# amg8833.net
KiCad netlist of a schematic drawn in EAGLE
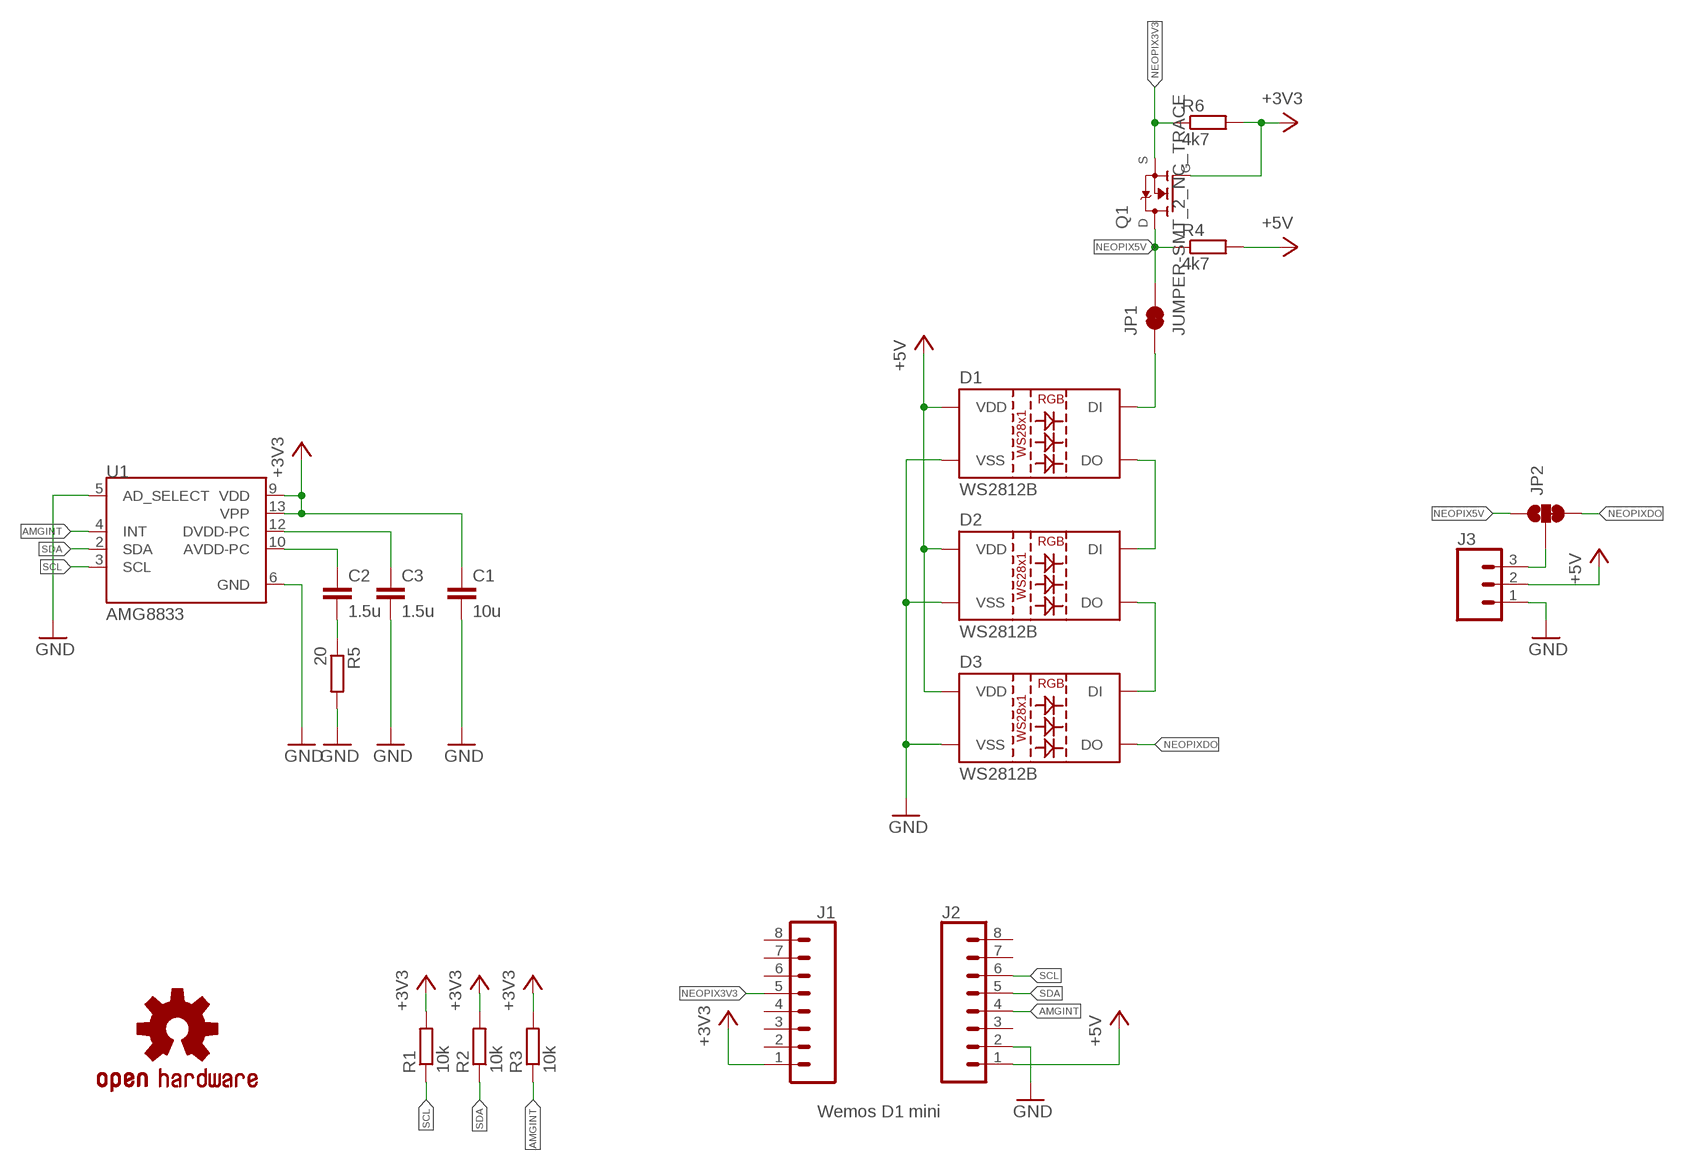
[diagram p0: schematic, sheet 1]

(export (version "E")
  (design (tool "Eeschema 10.0.6"))
  (components
    (comp (ref "C1")
      (value "10u")
      (footprint "eagle-import:C0603")
      (libsource (lib "eagle-import") (part "C-EUC0603"))
    )
    (comp (ref "C2")
      (value "1.5u")
      (footprint "eagle-import:C0603")
      (libsource (lib "eagle-import") (part "C-EUC0603"))
    )
    (comp (ref "C3")
      (value "1.5u")
      (footprint "eagle-import:C0603")
      (libsource (lib "eagle-import") (part "C-EUC0603"))
    )
    (comp (ref "D1")
      (value "WS2812B")
      (footprint "eagle-import:WS2812B")
      (libsource (lib "eagle-import") (part "WS2812B"))
    )
    (comp (ref "D2")
      (value "WS2812B")
      (footprint "eagle-import:WS2812B")
      (libsource (lib "eagle-import") (part "WS2812B"))
    )
    (comp (ref "D3")
      (value "WS2812B")
      (footprint "eagle-import:WS2812B")
      (libsource (lib "eagle-import") (part "WS2812B"))
    )
    (comp (ref "J1")
      (value "CONN_08")
      (footprint "eagle-import:1X08_LOCK_NO_SILK")
      (libsource (lib "eagle-import") (part "CONN_08"))
    )
    (comp (ref "J2")
      (value "CONN_08")
      (footprint "eagle-import:1X08_LOCK_NO_SILK")
      (libsource (lib "eagle-import") (part "CONN_08"))
    )
    (comp (ref "J3")
      (value "CONN_03SCREWTERMINAL-3.5MM-3-NS")
      (footprint "eagle-import:SCREWTERMINAL-3.5MM-3-NS")
      (libsource (lib "eagle-import") (part "CONN_03SCREWTERMINAL-3.5MM-3-NS"))
    )
    (comp (ref "JP1")
      (value "JUMPER-SMT_2_NC_TRACE")
      (footprint "eagle-import:SMT-JUMPER_2_NC_TRACE_SILK")
      (libsource (lib "eagle-import") (part "JUMPER-SMT_2_NC_TRACE"))
    )
    (comp (ref "JP2")
      (value "JUMPER-SMT_3_1-NC_TRACE")
      (footprint "eagle-import:SMT-JUMPER_3_1-NC_TRACE_SILK")
      (libsource (lib "eagle-import") (part "JUMPER-SMT_3_1-NC_TRACE"))
    )
    (comp (ref "LOGO1")
      (value "OSHW-LOGO")
      (footprint "eagle-import:OSHW-LOGO-M")
      (libsource (lib "eagle-import") (part "OSHW-LOGO"))
    )
    (comp (ref "Q1")
      (value "BSN20,215")
      (footprint "eagle-import:BSN20_215")
      (fields (field (name "MF") "NXP Semiconductors"))
      (libsource (lib "eagle-import") (part "BSN20,215"))
    )
    (comp (ref "R1")
      (value "10k")
      (footprint "eagle-import:R0603")
      (libsource (lib "eagle-import") (part "R-EU_R0603"))
    )
    (comp (ref "R2")
      (value "10k")
      (footprint "eagle-import:R0603")
      (libsource (lib "eagle-import") (part "R-EU_R0603"))
    )
    (comp (ref "R3")
      (value "10k")
      (footprint "eagle-import:R0603")
      (libsource (lib "eagle-import") (part "R-EU_R0603"))
    )
    (comp (ref "R4")
      (value "4k7")
      (footprint "eagle-import:R0603")
      (libsource (lib "eagle-import") (part "R-EU_R0603"))
    )
    (comp (ref "R5")
      (value "20")
      (footprint "eagle-import:R0603")
      (libsource (lib "eagle-import") (part "R-EU_R0603"))
    )
    (comp (ref "R6")
      (value "4k7")
      (footprint "eagle-import:R0603")
      (libsource (lib "eagle-import") (part "R-EU_R0603"))
    )
    (comp (ref "U1")
      (value "AMG8833")
      (footprint "eagle-import:XDCR_AMG8833")
      (fields (field (name "DIGI-KEY_PART_NUMBER") "P19002CT-ND") (field (name "MF") "Panasonic"))
      (libsource (lib "eagle-import") (part "AMG8833"))
    )
  )
  (nets
    (net (code "1") (name "+3V3") (class "Default")
      (node (ref "C1") (pin "1") (pinfunction "1_1") (pintype "passive"))
      (node (ref "J1") (pin "1") (pinfunction "1_1") (pintype "passive"))
      (node (ref "Q1") (pin "1") (pinfunction "G_1") (pintype "passive"))
      (node (ref "R1") (pin "2") (pinfunction "2_2") (pintype "passive"))
      (node (ref "R2") (pin "2") (pinfunction "2_2") (pintype "passive"))
      (node (ref "R3") (pin "2") (pinfunction "2_2") (pintype "passive"))
      (node (ref "R6") (pin "2") (pinfunction "2_2") (pintype "passive"))
      (node (ref "U1") (pin "13") (pinfunction "VPP_13") (pintype "power_in"))
      (node (ref "U1") (pin "9") (pinfunction "VDD_9") (pintype "power_in"))
    )
    (net (code "2") (name "+5V") (class "Default")
      (node (ref "D1") (pin "1") (pinfunction "VDD_1") (pintype "bidirectional"))
      (node (ref "D2") (pin "1") (pinfunction "VDD_1") (pintype "bidirectional"))
      (node (ref "D3") (pin "1") (pinfunction "VDD_1") (pintype "bidirectional"))
      (node (ref "J2") (pin "1") (pinfunction "1_1") (pintype "passive"))
      (node (ref "J3") (pin "2") (pinfunction "2_2") (pintype "passive"))
      (node (ref "R4") (pin "2") (pinfunction "2_2") (pintype "passive"))
    )
    (net (code "3") (name "AMGINT") (class "Default")
      (node (ref "J2") (pin "4") (pinfunction "4_4") (pintype "passive"))
      (node (ref "R3") (pin "1") (pinfunction "1_1") (pintype "passive"))
      (node (ref "U1") (pin "4") (pinfunction "INT_4") (pintype "bidirectional"))
    )
    (net (code "4") (name "GND") (class "Default")
      (node (ref "C1") (pin "2") (pinfunction "2_2") (pintype "passive"))
      (node (ref "C3") (pin "2") (pinfunction "2_2") (pintype "passive"))
      (node (ref "D1") (pin "3") (pinfunction "VSS_3") (pintype "bidirectional"))
      (node (ref "D2") (pin "3") (pinfunction "VSS_3") (pintype "bidirectional"))
      (node (ref "D3") (pin "3") (pinfunction "VSS_3") (pintype "bidirectional"))
      (node (ref "J2") (pin "2") (pinfunction "2_2") (pintype "passive"))
      (node (ref "J3") (pin "1") (pinfunction "1_1") (pintype "passive"))
      (node (ref "R5") (pin "2") (pinfunction "2_2") (pintype "passive"))
      (node (ref "U1") (pin "5") (pinfunction "AD_SELECT_5") (pintype "input"))
      (node (ref "U1") (pin "6") (pinfunction "GND_6") (pintype "power_in"))
    )
    (net (code "5") (name "NEOPIX3V3") (class "Default")
      (node (ref "J1") (pin "5") (pinfunction "5_5") (pintype "passive"))
      (node (ref "Q1") (pin "2") (pinfunction "S_2") (pintype "passive"))
      (node (ref "R6") (pin "1") (pinfunction "1_1") (pintype "passive"))
    )
    (net (code "6") (name "NEOPIX5V") (class "Default")
      (node (ref "JP1") (pin "2") (pinfunction "2_2") (pintype "passive"))
      (node (ref "JP2") (pin "1") (pinfunction "1_1") (pintype "passive"))
      (node (ref "Q1") (pin "3") (pinfunction "D_3") (pintype "passive"))
      (node (ref "R4") (pin "1") (pinfunction "1_1") (pintype "passive"))
    )
    (net (code "7") (name "NEOPIXDO") (class "Default")
      (node (ref "D3") (pin "2") (pinfunction "DO_2") (pintype "bidirectional"))
      (node (ref "JP2") (pin "3") (pinfunction "3_3") (pintype "passive"))
    )
    (net (code "8") (name "Net-(C2-Pad2)") (class "Default")
      (node (ref "C2") (pin "2") (pinfunction "2_2") (pintype "passive"))
      (node (ref "R5") (pin "1") (pinfunction "1_1") (pintype "passive"))
    )
    (net (code "9") (name "Net-(D1-DI)") (class "Default")
      (node (ref "D1") (pin "4") (pinfunction "DI_4") (pintype "bidirectional"))
      (node (ref "JP1") (pin "1") (pinfunction "1_1") (pintype "passive"))
    )
    (net (code "10") (name "Net-(D1-DO)") (class "Default")
      (node (ref "D1") (pin "2") (pinfunction "DO_2") (pintype "bidirectional"))
      (node (ref "D2") (pin "4") (pinfunction "DI_4") (pintype "bidirectional"))
    )
    (net (code "11") (name "Net-(D2-DO)") (class "Default")
      (node (ref "D2") (pin "2") (pinfunction "DO_2") (pintype "bidirectional"))
      (node (ref "D3") (pin "4") (pinfunction "DI_4") (pintype "bidirectional"))
    )
    (net (code "12") (name "Net-(J3-Pad3)") (class "Default")
      (node (ref "J3") (pin "3") (pinfunction "3_3") (pintype "passive"))
      (node (ref "JP2") (pin "2") (pinfunction "2_2") (pintype "passive"))
    )
    (net (code "13") (name "Net-(U1-AVDD-PC)") (class "Default")
      (node (ref "C2") (pin "1") (pinfunction "1_1") (pintype "passive"))
      (node (ref "U1") (pin "10") (pinfunction "AVDD-PC_10") (pintype "power_in"))
    )
    (net (code "14") (name "Net-(U1-DVDD-PC)") (class "Default")
      (node (ref "C3") (pin "1") (pinfunction "1_1") (pintype "passive"))
      (node (ref "U1") (pin "12") (pinfunction "DVDD-PC_12") (pintype "power_in"))
    )
    (net (code "15") (name "SCL") (class "Default")
      (node (ref "J2") (pin "6") (pinfunction "6_6") (pintype "passive"))
      (node (ref "R1") (pin "1") (pinfunction "1_1") (pintype "passive"))
      (node (ref "U1") (pin "3") (pinfunction "SCL_3") (pintype "bidirectional"))
    )
    (net (code "16") (name "SDA") (class "Default")
      (node (ref "J2") (pin "5") (pinfunction "5_5") (pintype "passive"))
      (node (ref "R2") (pin "1") (pinfunction "1_1") (pintype "passive"))
      (node (ref "U1") (pin "2") (pinfunction "SDA_2") (pintype "bidirectional"))
    )
    (net (code "17") (name "unconnected-(J1-Pad2)") (class "Default")
      (node (ref "J1") (pin "2") (pinfunction "2_2") (pintype "passive"))
    )
    (net (code "18") (name "unconnected-(J1-Pad3)") (class "Default")
      (node (ref "J1") (pin "3") (pinfunction "3_3") (pintype "passive"))
    )
    (net (code "19") (name "unconnected-(J1-Pad4)") (class "Default")
      (node (ref "J1") (pin "4") (pinfunction "4_4") (pintype "passive"))
    )
    (net (code "20") (name "unconnected-(J1-Pad6)") (class "Default")
      (node (ref "J1") (pin "6") (pinfunction "6_6") (pintype "passive"))
    )
    (net (code "21") (name "unconnected-(J1-Pad7)") (class "Default")
      (node (ref "J1") (pin "7") (pinfunction "7_7") (pintype "passive"))
    )
    (net (code "22") (name "unconnected-(J1-Pad8)") (class "Default")
      (node (ref "J1") (pin "8") (pinfunction "8_8") (pintype "passive"))
    )
    (net (code "23") (name "unconnected-(J2-Pad3)") (class "Default")
      (node (ref "J2") (pin "3") (pinfunction "3_3") (pintype "passive"))
    )
    (net (code "24") (name "unconnected-(J2-Pad7)") (class "Default")
      (node (ref "J2") (pin "7") (pinfunction "7_7") (pintype "passive"))
    )
    (net (code "25") (name "unconnected-(J2-Pad8)") (class "Default")
      (node (ref "J2") (pin "8") (pinfunction "8_8") (pintype "passive"))
    )
  )
)
